# MCU.net
KiCad netlist of a schematic drawn in Altium Designer
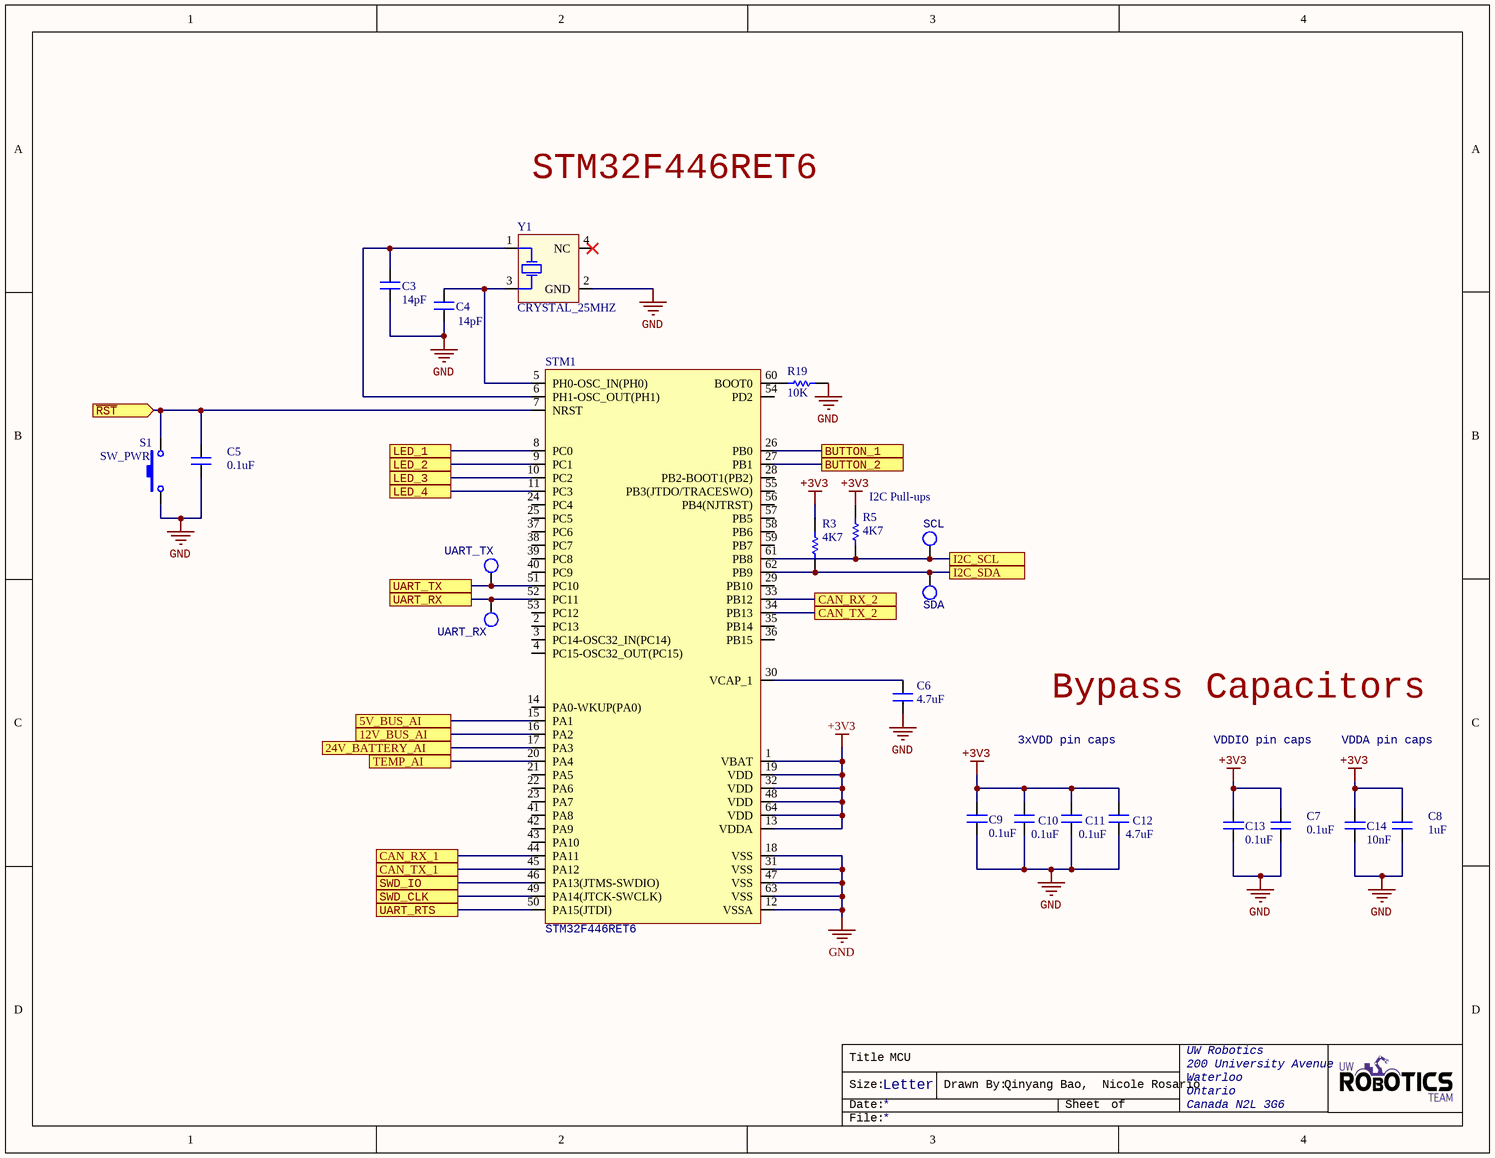
[diagram p0: MCU.SchDoc]

(export (version "E")
  (design (tool "Eeschema 10.0.6"))
  (components
    (comp (ref "C3")
      (value "14pF")
      (footprint "CAPC0603(1608)55_N")
      (description "Cap Ceramic 14pF 50V C0G 5% SMD 0603 125C Cardboard T/R")
      (fields (field (name "TOLERANCE") "5%") (field (name "Comment") "CL10C140JB8NNNC"))
      (libsource (lib "UWRT_Schematic_Library_2020") (part "CL10C140JB8NNNC"))
    )
    (comp (ref "C4")
      (value "14pF")
      (footprint "CAPC0603(1608)55_N")
      (description "Cap Ceramic 14pF 50V C0G 5% SMD 0603 125C Cardboard T/R")
      (fields (field (name "TOLERANCE") "5%") (field (name "Comment") "CL10C140JB8NNNC"))
      (libsource (lib "UWRT_Schematic_Library_2020") (part "CL10C140JB8NNNC"))
    )
    (comp (ref "C5")
      (value "0.1uF")
      (footprint "CAPC0603(1608)55_N")
      (description "CAP CER 0.1UF 16V X7R 0603")
      (fields (field (name "MANUFACTURER") "Yageo") (field (name "MPN") "CC0603KRX7R7BB104"))
      (libsource (lib "UWRT_Schematic_Library_2020") (part "CAP_0.1uF_16V_0603"))
    )
    (comp (ref "C6")
      (value "4.7uF")
      (footprint "CAPC0603(1608)55_N")
      (description "CAP CER 4.7UF 6.3V X5R 0603")
      (fields (field (name "MANUFACTURER") "Yageo") (field (name "MPN") "CC0603KRX5R5BB475"))
      (libsource (lib "UWRT_Schematic_Library_2020") (part "CAP_4.7uF_0603"))
    )
    (comp (ref "C7")
      (value "0.1uF")
      (footprint "CAPC0603(1608)55_N")
      (description "CAP CER 0.1UF 16V X7R 0603")
      (fields (field (name "MANUFACTURER") "Yageo") (field (name "MPN") "CC0603KRX7R7BB104"))
      (libsource (lib "UWRT_Schematic_Library_2020") (part "CAP_0.1uF_16V_0603"))
    )
    (comp (ref "C8")
      (value "1uF")
      (footprint "CAPC0603(1608)55_N")
      (description "CAP CER 1UF 16V Y5V 0603")
      (fields (field (name "MANUFACTURER") "Yageo") (field (name "MPN") "CC0603ZRY5V7BB105"))
      (libsource (lib "UWRT_Schematic_Library_2020") (part "CAP_1uF_16V_0603"))
    )
    (comp (ref "C9")
      (value "0.1uF")
      (footprint "CAPC0603(1608)55_N")
      (description "CAP CER 0.1UF 16V X7R 0603")
      (fields (field (name "MANUFACTURER") "Yageo") (field (name "MPN") "CC0603KRX7R7BB104"))
      (libsource (lib "UWRT_Schematic_Library_2020") (part "CAP_0.1uF_16V_0603"))
    )
    (comp (ref "C10")
      (value "0.1uF")
      (footprint "CAPC0603(1608)55_N")
      (description "CAP CER 0.1UF 16V X7R 0603")
      (fields (field (name "MANUFACTURER") "Yageo") (field (name "MPN") "CC0603KRX7R7BB104"))
      (libsource (lib "UWRT_Schematic_Library_2020") (part "CAP_0.1uF_16V_0603"))
    )
    (comp (ref "C11")
      (value "0.1uF")
      (footprint "CAPC0603(1608)55_N")
      (description "CAP CER 0.1UF 16V X7R 0603")
      (fields (field (name "MANUFACTURER") "Yageo") (field (name "MPN") "CC0603KRX7R7BB104"))
      (libsource (lib "UWRT_Schematic_Library_2020") (part "CAP_0.1uF_16V_0603"))
    )
    (comp (ref "C12")
      (value "4.7uF")
      (footprint "CAPC0603(1608)55_N")
      (description "CAP CER 4.7UF 6.3V X5R 0603")
      (fields (field (name "MANUFACTURER") "Yageo") (field (name "MPN") "CC0603KRX5R5BB475"))
      (libsource (lib "UWRT_Schematic_Library_2020") (part "CAP_4.7uF_0603"))
    )
    (comp (ref "C13")
      (value "0.1uF")
      (footprint "CAPC0603(1608)55_N")
      (description "CAP CER 0.1UF 16V X7R 0603")
      (fields (field (name "MANUFACTURER") "Yageo") (field (name "MPN") "CC0603KRX7R7BB104"))
      (libsource (lib "UWRT_Schematic_Library_2020") (part "CAP_0.1uF_16V_0603"))
    )
    (comp (ref "C14")
      (value "10nF")
      (footprint "CAPC0603(1608)55_N")
      (description "CAP CER 10000PF 16V X7R 0603")
      (fields (field (name "MANUFACTURER") "Yageo") (field (name "MPN") "CC0603KRX7R7BB103"))
      (libsource (lib "UWRT_Schematic_Library_2020") (part "CAP_10nF_0603"))
    )
    (comp (ref "R3")
      (value "4K7")
      (footprint "RESC0603(1608)_N")
      (description "RES SMD 4.7K OHM 5% 1/10W 0603")
      (fields (field (name "MANUFACTURER") "Yageo") (field (name "TOLERANCE") "5%"))
      (libsource (lib "UWRT_Schematic_Library_2020") (part "RES_4K7_0603"))
    )
    (comp (ref "R5")
      (value "4K7")
      (footprint "RESC0603(1608)_N")
      (description "RES SMD 4.7K OHM 5% 1/10W 0603")
      (fields (field (name "MANUFACTURER") "Yageo") (field (name "TOLERANCE") "5%"))
      (libsource (lib "UWRT_Schematic_Library_2020") (part "RES_4K7_0603"))
    )
    (comp (ref "R19")
      (value "10K")
      (footprint "RESC0603(1608)_N")
      (description "RES SMD 10K OHM 5% 1/10W 0603")
      (fields (field (name "MANUFACTURER") "Yageo") (field (name "MPN") "RC0603JR-0710KL"))
      (libsource (lib "UWRT_Schematic_Library_2020") (part "RES_10K_0603"))
    )
    (comp (ref "S1")
      (value "SW_PWR")
      (footprint "PTS830GM140")
      (description "Power Switch (Red)")
      (fields (field (name "MPN") "PTS830GM140 SMTR LFS") (field (name "MANUFACTURER") "C&K"))
      (libsource (lib "UWRT_Schematic_Library_2020") (part "SW_PWR"))
    )
    (comp (ref "SCL")
      (value "TESTPOINT_LOOP")
      (footprint "TESTPOINT_LOOP")
      (description "Loop testpoint through-hole pad")
      (fields (field (name "MANUFACTURER") "Keystone Electronics"))
      (libsource (lib "UWRT_Schematic_Library_2020") (part "TESTPOINT_LOOP"))
    )
    (comp (ref "SDA")
      (value "TESTPOINT_LOOP")
      (footprint "TESTPOINT_LOOP")
      (description "Loop testpoint through-hole pad")
      (fields (field (name "MANUFACTURER") "Keystone Electronics"))
      (libsource (lib "UWRT_Schematic_Library_2020") (part "TESTPOINT_LOOP"))
    )
    (comp (ref "STM1")
      (value "STM32F446RET6")
      (footprint "STM-LQFP64_L")
      (libsource (lib "UWRT_Schematic_Library_2020") (part "MCU_STM32F446RET6"))
    )
    (comp (ref "UART_RX")
      (value "TESTPOINT_LOOP")
      (footprint "TESTPOINT_LOOP")
      (description "Loop testpoint through-hole pad")
      (fields (field (name "MANUFACTURER") "Keystone Electronics"))
      (libsource (lib "UWRT_Schematic_Library_2020") (part "TESTPOINT_LOOP"))
    )
    (comp (ref "UART_TX")
      (value "TESTPOINT_LOOP")
      (footprint "TESTPOINT_LOOP")
      (description "Loop testpoint through-hole pad")
      (fields (field (name "MANUFACTURER") "Keystone Electronics"))
      (libsource (lib "UWRT_Schematic_Library_2020") (part "TESTPOINT_LOOP"))
    )
    (comp (ref "Y1")
      (value "CRYSTAL_25MHZ")
      (footprint "AVX-CX2520DB32000D0GEJZ1-4_V")
      (description "CRYSTAL 25.0000MHZ 12PF SMD")
      (libsource (lib "UWRT_Schematic_Library_2020") (part "CRYSTAL_25MHZ"))
    )
  )
  (nets
    (net (code "1") (name "+3V3") (class "Default")
      (node (ref "C10") (pin "2") (pinfunction "2_2") (pintype "passive"))
      (node (ref "C11") (pin "2") (pinfunction "2_2") (pintype "passive"))
      (node (ref "C12") (pin "2") (pinfunction "2_2") (pintype "passive"))
      (node (ref "C13") (pin "2") (pinfunction "2_2") (pintype "passive"))
      (node (ref "C14") (pin "2") (pinfunction "2_2") (pintype "passive"))
      (node (ref "C7") (pin "2") (pinfunction "2_2") (pintype "passive"))
      (node (ref "C8") (pin "2") (pinfunction "2_2") (pintype "passive"))
      (node (ref "C9") (pin "2") (pinfunction "2_2") (pintype "passive"))
      (node (ref "R3") (pin "2") (pinfunction "2_2") (pintype "passive"))
      (node (ref "R5") (pin "2") (pinfunction "2_2") (pintype "passive"))
      (node (ref "STM1") (pin "1") (pinfunction "VBAT_1") (pintype "power_in"))
      (node (ref "STM1") (pin "13") (pinfunction "VDDA_13") (pintype "power_in"))
      (node (ref "STM1") (pin "19") (pinfunction "VDD_19") (pintype "power_in"))
      (node (ref "STM1") (pin "32") (pinfunction "VDD_32") (pintype "power_in"))
      (node (ref "STM1") (pin "48") (pinfunction "VDD_48") (pintype "power_in"))
      (node (ref "STM1") (pin "64") (pinfunction "VDD_64") (pintype "power_in"))
    )
    (net (code "2") (name "/5V_BUS_AI") (class "Default")
      (node (ref "STM1") (pin "15") (pinfunction "PA1_15") (pintype "bidirectional"))
    )
    (net (code "3") (name "/12V_BUS_AI") (class "Default")
      (node (ref "STM1") (pin "16") (pinfunction "PA2_16") (pintype "bidirectional"))
    )
    (net (code "4") (name "/24V_BATTERY_AI") (class "Default")
      (node (ref "STM1") (pin "17") (pinfunction "PA3_17") (pintype "bidirectional"))
    )
    (net (code "5") (name "/BUTTON_1") (class "Default")
      (node (ref "STM1") (pin "26") (pinfunction "PB0_26") (pintype "bidirectional"))
    )
    (net (code "6") (name "/BUTTON_2") (class "Default")
      (node (ref "STM1") (pin "27") (pinfunction "PB1_27") (pintype "bidirectional"))
    )
    (net (code "7") (name "/CAN_RX_1") (class "Default")
      (node (ref "STM1") (pin "44") (pinfunction "PA11_44") (pintype "bidirectional"))
    )
    (net (code "8") (name "/CAN_RX_2") (class "Default")
      (node (ref "STM1") (pin "33") (pinfunction "PB12_33") (pintype "bidirectional"))
    )
    (net (code "9") (name "/CAN_TX_1") (class "Default")
      (node (ref "STM1") (pin "45") (pinfunction "PA12_45") (pintype "bidirectional"))
    )
    (net (code "10") (name "/CAN_TX_2") (class "Default")
      (node (ref "STM1") (pin "34") (pinfunction "PB13_34") (pintype "bidirectional"))
    )
    (net (code "11") (name "/I2C_SCL") (class "Default")
      (node (ref "R5") (pin "1") (pinfunction "1_1") (pintype "passive"))
      (node (ref "SCL") (pin "1") (pintype "passive"))
      (node (ref "STM1") (pin "61") (pinfunction "PB8_61") (pintype "bidirectional"))
    )
    (net (code "12") (name "/I2C_SDA") (class "Default")
      (node (ref "R3") (pin "1") (pinfunction "1_1") (pintype "passive"))
      (node (ref "SDA") (pin "1") (pintype "passive"))
      (node (ref "STM1") (pin "62") (pinfunction "PB9_62") (pintype "bidirectional"))
    )
    (net (code "13") (name "/LED_1") (class "Default")
      (node (ref "STM1") (pin "8") (pinfunction "PC0_8") (pintype "bidirectional"))
    )
    (net (code "14") (name "/LED_2") (class "Default")
      (node (ref "STM1") (pin "9") (pinfunction "PC1_9") (pintype "bidirectional"))
    )
    (net (code "15") (name "/LED_3") (class "Default")
      (node (ref "STM1") (pin "10") (pinfunction "PC2_10") (pintype "bidirectional"))
    )
    (net (code "16") (name "/LED_4") (class "Default")
      (node (ref "STM1") (pin "11") (pinfunction "PC3_11") (pintype "bidirectional"))
    )
    (net (code "17") (name "/SWD_CLK") (class "Default")
      (node (ref "STM1") (pin "49") (pinfunction "PA14(JTCK-SWCLK)_49") (pintype "bidirectional"))
    )
    (net (code "18") (name "/SWD_IO") (class "Default")
      (node (ref "STM1") (pin "46") (pinfunction "PA13(JTMS-SWDIO)_46") (pintype "bidirectional"))
    )
    (net (code "19") (name "/TEMP_AI") (class "Default")
      (node (ref "STM1") (pin "20") (pinfunction "PA4_20") (pintype "bidirectional"))
    )
    (net (code "20") (name "/UART_RTS") (class "Default")
      (node (ref "STM1") (pin "50") (pinfunction "PA15(JTDI)_50") (pintype "bidirectional"))
    )
    (net (code "21") (name "/UART_RX") (class "Default")
      (node (ref "STM1") (pin "52") (pinfunction "PC11_52") (pintype "bidirectional"))
      (node (ref "UART_RX") (pin "1") (pintype "passive"))
    )
    (net (code "22") (name "/UART_TX") (class "Default")
      (node (ref "STM1") (pin "51") (pinfunction "PC10_51") (pintype "bidirectional"))
      (node (ref "UART_TX") (pin "1") (pintype "passive"))
    )
    (net (code "23") (name "/~{RST}") (class "Default")
      (node (ref "C5") (pin "2") (pinfunction "2_2") (pintype "passive"))
      (node (ref "S1") (pin "2") (pinfunction "2_2") (pintype "passive"))
      (node (ref "STM1") (pin "7") (pinfunction "NRST_7") (pintype "bidirectional"))
    )
    (net (code "24") (name "GND") (class "Default")
      (node (ref "C10") (pin "1") (pinfunction "1_1") (pintype "passive"))
      (node (ref "C11") (pin "1") (pinfunction "1_1") (pintype "passive"))
      (node (ref "C12") (pin "1") (pinfunction "1_1") (pintype "passive"))
      (node (ref "C13") (pin "1") (pinfunction "1_1") (pintype "passive"))
      (node (ref "C14") (pin "1") (pinfunction "1_1") (pintype "passive"))
      (node (ref "C3") (pin "1") (pinfunction "1_1") (pintype "passive"))
      (node (ref "C4") (pin "1") (pinfunction "1_1") (pintype "passive"))
      (node (ref "C5") (pin "1") (pinfunction "1_1") (pintype "passive"))
      (node (ref "C6") (pin "1") (pinfunction "1_1") (pintype "passive"))
      (node (ref "C7") (pin "1") (pinfunction "1_1") (pintype "passive"))
      (node (ref "C8") (pin "1") (pinfunction "1_1") (pintype "passive"))
      (node (ref "C9") (pin "1") (pinfunction "1_1") (pintype "passive"))
      (node (ref "R19") (pin "1") (pinfunction "1_1") (pintype "passive"))
      (node (ref "S1") (pin "1") (pinfunction "1_1") (pintype "passive"))
      (node (ref "STM1") (pin "12") (pinfunction "VSSA_12") (pintype "power_in"))
      (node (ref "STM1") (pin "18") (pinfunction "VSS_18") (pintype "power_in"))
      (node (ref "STM1") (pin "31") (pinfunction "VSS_31") (pintype "power_in"))
      (node (ref "STM1") (pin "47") (pinfunction "VSS_47") (pintype "power_in"))
      (node (ref "STM1") (pin "63") (pinfunction "VSS_63") (pintype "power_in"))
      (node (ref "Y1") (pin "2") (pinfunction "GND_2") (pintype "power_in"))
    )
    (net (code "25") (name "Net-(STM1-BOOT0)") (class "Default")
      (node (ref "R19") (pin "2") (pinfunction "2_2") (pintype "passive"))
      (node (ref "STM1") (pin "60") (pinfunction "BOOT0_60") (pintype "bidirectional"))
    )
    (net (code "26") (name "Net-(STM1-PH0-OSC_IN(PH0))") (class "Default")
      (node (ref "C4") (pin "2") (pinfunction "2_2") (pintype "passive"))
      (node (ref "STM1") (pin "5") (pinfunction "PH0-OSC_IN(PH0)_5") (pintype "bidirectional"))
      (node (ref "Y1") (pin "3") (pinfunction "HOT_3") (pintype "passive"))
    )
    (net (code "27") (name "Net-(STM1-PH1-OSC_OUT(PH1))") (class "Default")
      (node (ref "C3") (pin "2") (pinfunction "2_2") (pintype "passive"))
      (node (ref "STM1") (pin "6") (pinfunction "PH1-OSC_OUT(PH1)_6") (pintype "bidirectional"))
      (node (ref "Y1") (pin "1") (pinfunction "HOT_1") (pintype "passive"))
    )
    (net (code "28") (name "Net-(STM1-VCAP_1)") (class "Default")
      (node (ref "C6") (pin "2") (pinfunction "2_2") (pintype "passive"))
      (node (ref "STM1") (pin "30") (pinfunction "VCAP_1_30") (pintype "passive"))
    )
    (net (code "29") (name "unconnected-(STM1-PA0-WKUP(PA0)-Pad14)") (class "Default")
      (node (ref "STM1") (pin "14") (pinfunction "PA0-WKUP(PA0)_14") (pintype "bidirectional"))
    )
    (net (code "30") (name "unconnected-(STM1-PA5-Pad21)") (class "Default")
      (node (ref "STM1") (pin "21") (pinfunction "PA5_21") (pintype "bidirectional"))
    )
    (net (code "31") (name "unconnected-(STM1-PA6-Pad22)") (class "Default")
      (node (ref "STM1") (pin "22") (pinfunction "PA6_22") (pintype "bidirectional"))
    )
    (net (code "32") (name "unconnected-(STM1-PA7-Pad23)") (class "Default")
      (node (ref "STM1") (pin "23") (pinfunction "PA7_23") (pintype "bidirectional"))
    )
    (net (code "33") (name "unconnected-(STM1-PA8-Pad41)") (class "Default")
      (node (ref "STM1") (pin "41") (pinfunction "PA8_41") (pintype "bidirectional"))
    )
    (net (code "34") (name "unconnected-(STM1-PA9-Pad42)") (class "Default")
      (node (ref "STM1") (pin "42") (pinfunction "PA9_42") (pintype "bidirectional"))
    )
    (net (code "35") (name "unconnected-(STM1-PA10-Pad43)") (class "Default")
      (node (ref "STM1") (pin "43") (pinfunction "PA10_43") (pintype "bidirectional"))
    )
    (net (code "36") (name "unconnected-(STM1-PB2-BOOT1(PB2)-Pad28)") (class "Default")
      (node (ref "STM1") (pin "28") (pinfunction "PB2-BOOT1(PB2)_28") (pintype "bidirectional"))
    )
    (net (code "37") (name "unconnected-(STM1-PB3(JTDO{slash}TRACESWO)-Pad55)") (class "Default")
      (node (ref "STM1") (pin "55") (pinfunction "PB3(JTDO/TRACESWO)_55") (pintype "bidirectional"))
    )
    (net (code "38") (name "unconnected-(STM1-PB4(NJTRST)-Pad56)") (class "Default")
      (node (ref "STM1") (pin "56") (pinfunction "PB4(NJTRST)_56") (pintype "bidirectional"))
    )
    (net (code "39") (name "unconnected-(STM1-PB5-Pad57)") (class "Default")
      (node (ref "STM1") (pin "57") (pinfunction "PB5_57") (pintype "bidirectional"))
    )
    (net (code "40") (name "unconnected-(STM1-PB6-Pad58)") (class "Default")
      (node (ref "STM1") (pin "58") (pinfunction "PB6_58") (pintype "bidirectional"))
    )
    (net (code "41") (name "unconnected-(STM1-PB7-Pad59)") (class "Default")
      (node (ref "STM1") (pin "59") (pinfunction "PB7_59") (pintype "bidirectional"))
    )
    (net (code "42") (name "unconnected-(STM1-PB10-Pad29)") (class "Default")
      (node (ref "STM1") (pin "29") (pinfunction "PB10_29") (pintype "bidirectional"))
    )
    (net (code "43") (name "unconnected-(STM1-PB14-Pad35)") (class "Default")
      (node (ref "STM1") (pin "35") (pinfunction "PB14_35") (pintype "bidirectional"))
    )
    (net (code "44") (name "unconnected-(STM1-PB15-Pad36)") (class "Default")
      (node (ref "STM1") (pin "36") (pinfunction "PB15_36") (pintype "bidirectional"))
    )
    (net (code "45") (name "unconnected-(STM1-PC4-Pad24)") (class "Default")
      (node (ref "STM1") (pin "24") (pinfunction "PC4_24") (pintype "bidirectional"))
    )
    (net (code "46") (name "unconnected-(STM1-PC5-Pad25)") (class "Default")
      (node (ref "STM1") (pin "25") (pinfunction "PC5_25") (pintype "bidirectional"))
    )
    (net (code "47") (name "unconnected-(STM1-PC6-Pad37)") (class "Default")
      (node (ref "STM1") (pin "37") (pinfunction "PC6_37") (pintype "bidirectional"))
    )
    (net (code "48") (name "unconnected-(STM1-PC7-Pad38)") (class "Default")
      (node (ref "STM1") (pin "38") (pinfunction "PC7_38") (pintype "bidirectional"))
    )
    (net (code "49") (name "unconnected-(STM1-PC8-Pad39)") (class "Default")
      (node (ref "STM1") (pin "39") (pinfunction "PC8_39") (pintype "bidirectional"))
    )
    (net (code "50") (name "unconnected-(STM1-PC9-Pad40)") (class "Default")
      (node (ref "STM1") (pin "40") (pinfunction "PC9_40") (pintype "bidirectional"))
    )
    (net (code "51") (name "unconnected-(STM1-PC12-Pad53)") (class "Default")
      (node (ref "STM1") (pin "53") (pinfunction "PC12_53") (pintype "bidirectional"))
    )
    (net (code "52") (name "unconnected-(STM1-PC13-Pad2)") (class "Default")
      (node (ref "STM1") (pin "2") (pinfunction "PC13_2") (pintype "bidirectional"))
    )
    (net (code "53") (name "unconnected-(STM1-PC14-OSC32_IN(PC14)-Pad3)") (class "Default")
      (node (ref "STM1") (pin "3") (pinfunction "PC14-OSC32_IN(PC14)_3") (pintype "bidirectional"))
    )
    (net (code "54") (name "unconnected-(STM1-PC15-OSC32_OUT(PC15)-Pad4)") (class "Default")
      (node (ref "STM1") (pin "4") (pinfunction "PC15-OSC32_OUT(PC15)_4") (pintype "bidirectional"))
    )
    (net (code "55") (name "unconnected-(STM1-PD2-Pad54)") (class "Default")
      (node (ref "STM1") (pin "54") (pinfunction "PD2_54") (pintype "bidirectional"))
    )
    (net (code "56") (name "unconnected-(Y1-NC-Pad4)") (class "Default")
      (node (ref "Y1") (pin "4") (pinfunction "NC_4") (pintype "passive+no_connect"))
    )
  )
)
